# Sheet2.net
KiCad netlist of a schematic drawn in Altium Designer
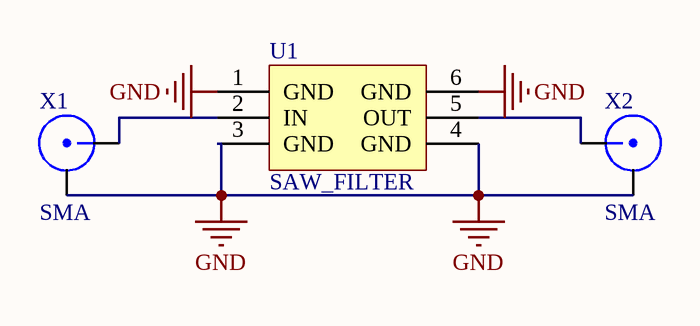
[diagram p0: Sheet2.SchDoc]

(export (version "E")
  (design (tool "Eeschema 10.0.6"))
  (components
    (comp (ref "U1")
      (value "SAW_FILTER")
      (footprint "SAW_3.0")
      (libsource (lib "Library") (part "SAW_FILTER"))
    )
    (comp (ref "X1") (value "SMA") (footprint "SMA1") (libsource (lib "") (part "SMA_1")))
    (comp (ref "X2") (value "SMA") (footprint "SMA1") (libsource (lib "Library") (part "SMA")))
  )
  (nets
    (net (code "1") (name "GND") (class "Default")
      (node (ref "U1") (pin "1") (pinfunction "GND_1") (pintype "passive"))
      (node (ref "U1") (pin "3") (pinfunction "GND_3") (pintype "passive"))
      (node (ref "U1") (pin "4") (pinfunction "GND_4") (pintype "passive"))
      (node (ref "U1") (pin "6") (pinfunction "GND_6") (pintype "passive"))
      (node (ref "X1") (pin "2") (pinfunction "2_2") (pintype "passive"))
      (node (ref "X2") (pin "2") (pinfunction "2_2") (pintype "passive"))
    )
    (net (code "2") (name "Net-(U1-IN)") (class "Default")
      (node (ref "U1") (pin "2") (pinfunction "IN_2") (pintype "passive"))
      (node (ref "X1") (pin "1") (pinfunction "1_1") (pintype "passive"))
    )
    (net (code "3") (name "Net-(U1-OUT)") (class "Default")
      (node (ref "U1") (pin "5") (pinfunction "OUT_5") (pintype "passive"))
      (node (ref "X2") (pin "1") (pinfunction "1_1") (pintype "passive"))
    )
  )
)
